# 02_FPGA_Clock_Flash.net
KiCad netlist of a schematic drawn in Altium Designer
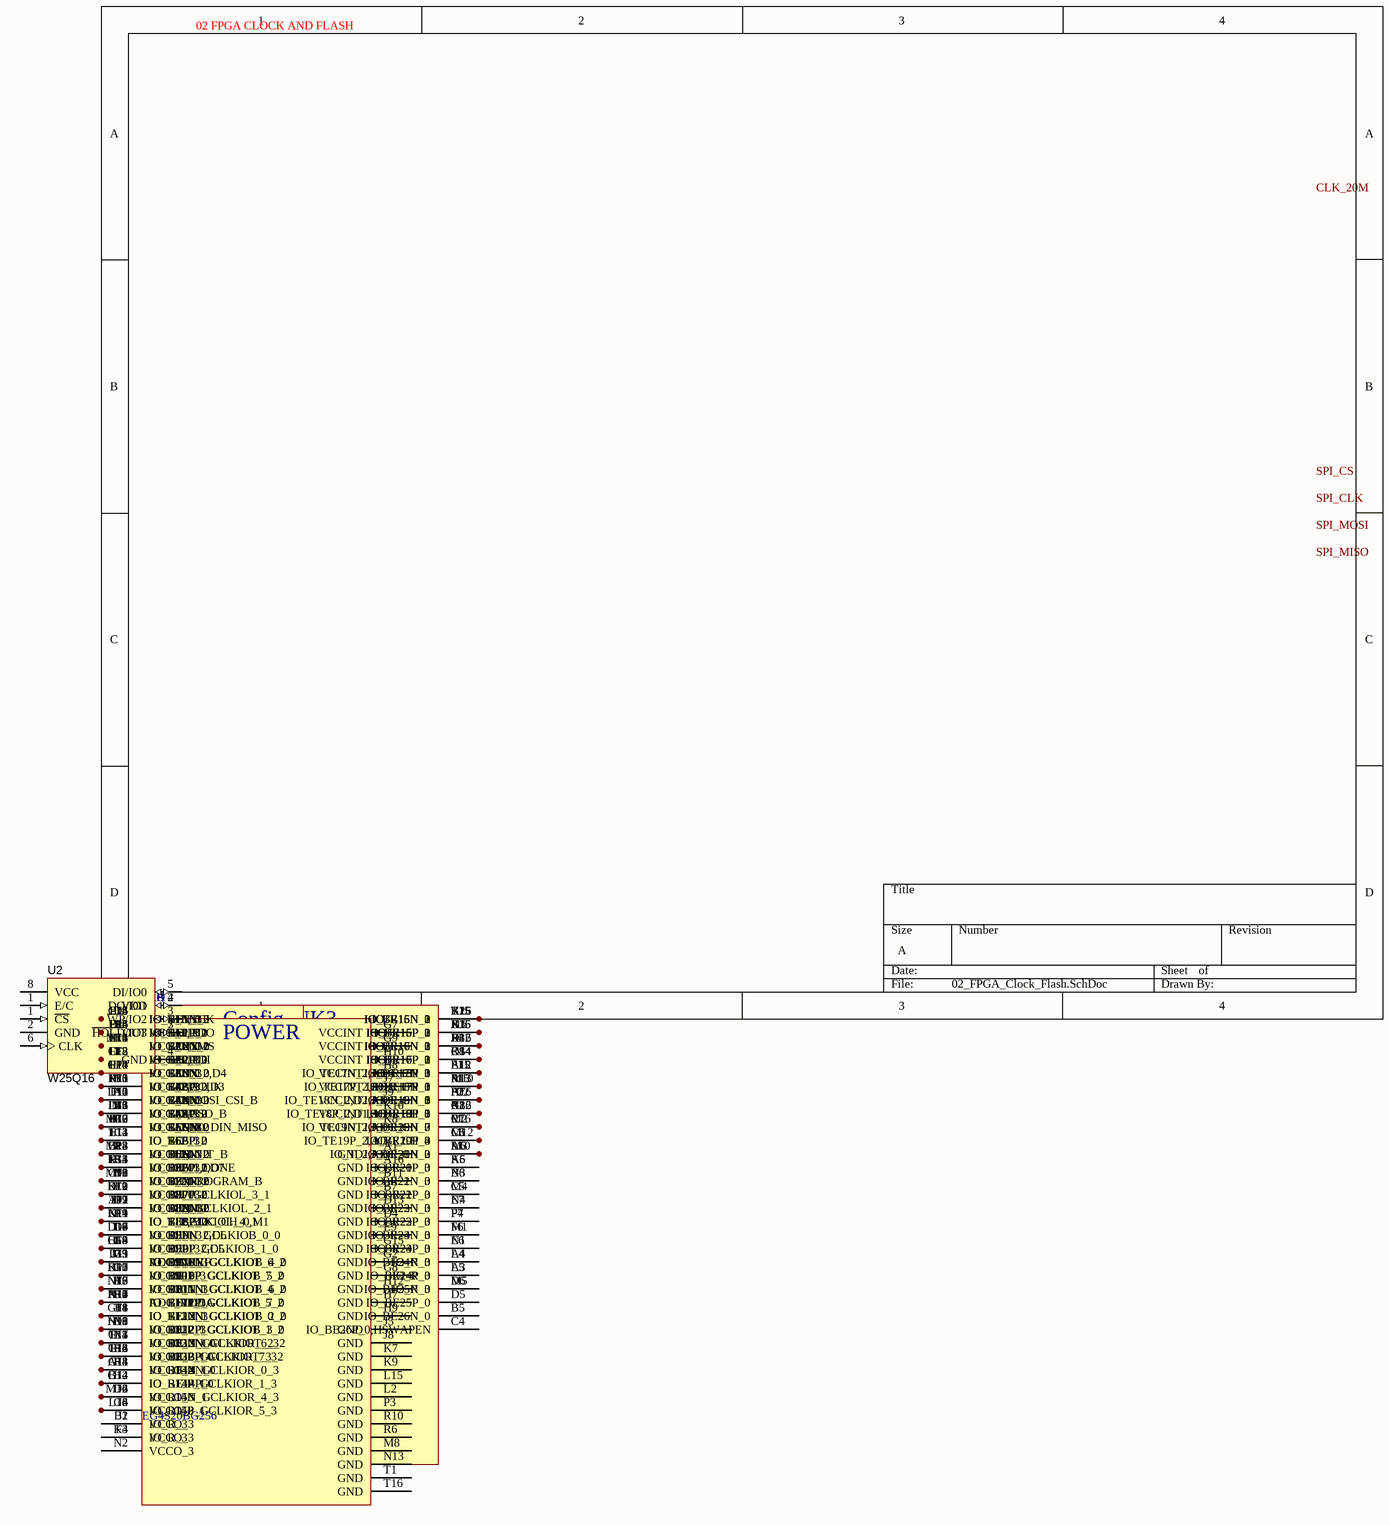
[diagram p0: 02_FPGA_Clock_Flash.SchDoc]

(export (version "E")
  (design (tool "Eeschema 10.0.6"))
  (components
    (comp (ref "U1") (value "EG4S20BG256") (footprint "FBGA256") (libsource (lib "") (part "EG4S20BG256_4")))
    (comp (ref "U2")
      (value "W25Q16")
      (footprint "MICT-MW-8_N")
      (description "2.5V 8M-Bit Serial Flash Memory with Dual and Quad SPI, SOIC-8")
      (fields
        (field (name "PARTNUMBER") "W25Q16")
        (field (name "MANUFACTURER") "Winbond")
        (field (name "SYMBOLCREATOR") "Altium")
        (field (name "PUBLISHER") "Texas Instruments")
      )
      (libsource (lib "Other_IC") (part "W25Q80BLSNIG"))
    )
    (comp (ref "Y1")
      (value "7X-50.000MBB-T")
      (footprint "XTAL_NX3225SA")
      (description "Crystal, 有源晶振，Sealed Locked 50MHz, 15pF, SMD")
      (fields
        (field (name "MANUFACTURER") "TXC Corporation")
        (field (name "FREQUENCY") "50MHz")
        (field (name "SYMBOLCREATOR") "a0799628")
        (field (name "PUBLISHER") "Texas Instruments")
      )
      (libsource (lib "HPA_SCHLIB") (part "7X-20.000MBB-T_1"))
    )
  )
  (nets
    (net (code "6") (name "Net-(U1A-IO_BE1N_0)") (class "Default")
      (node (ref "U1") (pin "C14") (pinfunction "IO_B_0,TCK_C14") (pintype "passive"))
      (node (ref "U1") (pin "D3") (pinfunction "IO_R1N_3_D3") (pintype "passive"))
      (node (ref "U1") (pin "F16") (pinfunction "IO_BE1N_0_F16") (pintype "passive"))
      (node (ref "U1") (pin "P15") (pinfunction "IO_L1N_1_P15") (pintype "passive"))
      (node (ref "U1") (pin "T4") (pinfunction "IO_TE1N_2_T4") (pintype "passive"))
    )
    (net (code "7") (name "Net-(U1A-IO_BE1P_0)") (class "Default")
      (node (ref "U1") (pin "B3") (pinfunction "IO_R1P_3_B3") (pintype "passive"))
      (node (ref "U1") (pin "E14") (pinfunction "IO_L_1,TDO_E14") (pintype "passive"))
      (node (ref "U1") (pin "E16") (pinfunction "IO_BE1P_0_E16") (pintype "passive"))
      (node (ref "U1") (pin "E5") (pinfunction "VCCAUX_E5") (pintype "passive"))
      (node (ref "U1") (pin "P16") (pinfunction "IO_L1P_1_P16") (pintype "passive"))
      (node (ref "U1") (pin "P6") (pinfunction "IO_TE1P_2_P6") (pintype "passive"))
    )
    (net (code "8") (name "Net-(U1A-IO_BE2N_0)") (class "Default")
      (node (ref "U1") (pin "A15") (pinfunction "IO_L_1,TMS_A15") (pintype "passive"))
      (node (ref "U1") (pin "E12") (pinfunction "IO_BE2N_0_E12") (pintype "passive"))
      (node (ref "U1") (pin "E4") (pinfunction "IO_R2N_3_E4") (pintype "passive"))
      (node (ref "U1") (pin "F11") (pinfunction "VCCAUX_F11") (pintype "passive"))
      (node (ref "U1") (pin "M11") (pinfunction "IO_L2N_1_M11") (pintype "passive"))
      (node (ref "U1") (pin "T6") (pinfunction "IO_TE2N_2_T6") (pintype "passive"))
    )
    (net (code "9") (name "Net-(U1A-IO_BE2P_0)") (class "Default")
      (node (ref "U1") (pin "C12") (pinfunction "IO_B_0,TDI_C12") (pintype "passive"))
      (node (ref "U1") (pin "E3") (pinfunction "IO_R2P_3_E3") (pintype "passive"))
      (node (ref "U1") (pin "F12") (pinfunction "IO_BE2P_0_F12") (pintype "passive"))
      (node (ref "U1") (pin "F8") (pinfunction "VCCAUX_F8") (pintype "passive"))
      (node (ref "U1") (pin "L12") (pinfunction "IO_L2P_1_L12") (pintype "passive"))
      (node (ref "U1") (pin "T5") (pinfunction "IO_TE2P_2_T5") (pintype "passive"))
    )
    (net (code "10") (name "Net-(U1A-IO_BE3N_0)") (class "Default")
      (node (ref "U1") (pin "F4") (pinfunction "IO_R3N_3_F4") (pintype "passive"))
      (node (ref "U1") (pin "G10") (pinfunction "VCCAUX_G10") (pintype "passive"))
      (node (ref "U1") (pin "H11") (pinfunction "IO_BE3N_0_H11") (pintype "passive"))
      (node (ref "U1") (pin "P14") (pinfunction "IO_L3N_1_P14") (pintype "passive"))
      (node (ref "U1") (pin "P5") (pinfunction "IO_TE3N_2,D4_P5") (pintype "passive"))
    )
    (net (code "11") (name "Net-(U1A-IO_BE3P_0)") (class "Default")
      (node (ref "U1") (pin "F10") (pinfunction "IO_BE3P_0_F10") (pintype "passive"))
      (node (ref "U1") (pin "F5") (pinfunction "IO_R3P_3_F5") (pintype "passive"))
      (node (ref "U1") (pin "H6") (pinfunction "VCCAUX_H6") (pintype "passive"))
      (node (ref "U1") (pin "K11") (pinfunction "IO_L4P_1_K11") (pintype "passive"))
      (node (ref "U1") (pin "N5") (pinfunction "IO_TE3P_2,D3_N5") (pintype "passive"))
      (node (ref "U1") (pin "R11") (pinfunction "IO_T_2,CCLK_R11") (pintype "passive"))
    )
    (net (code "12") (name "Net-(U1A-IO_BE4N_0)") (class "Default")
      (node (ref "U1") (pin "A2") (pinfunction "IO_R4N_3_A2") (pintype "passive"))
      (node (ref "U1") (pin "D12") (pinfunction "IO_BE4N_0_D12") (pintype "passive"))
      (node (ref "U1") (pin "J10") (pinfunction "VCCAUX_J10") (pintype "passive"))
      (node (ref "U1") (pin "J11") (pinfunction "IO_L4N_1_J11") (pintype "passive"))
      (node (ref "U1") (pin "N6") (pinfunction "IO_TE4N_2_N6") (pintype "passive"))
      (node (ref "U1") (pin "T10") (pinfunction "IO_T_2,MOSI_CSI_B_T10") (pintype "passive"))
    )
    (net (code "13") (name "Net-(U1A-IO_BE4P_0)") (class "Default")
      (node (ref "U1") (pin "B2") (pinfunction "IO_R4P_3_B2") (pintype "passive"))
      (node (ref "U1") (pin "D11") (pinfunction "IO_BE4P_0_D11") (pintype "passive"))
      (node (ref "U1") (pin "L13") (pinfunction "IO_L5P_1_L13") (pintype "passive"))
      (node (ref "U1") (pin "L6") (pinfunction "VCCAUX_L6") (pintype "passive"))
      (node (ref "U1") (pin "M6") (pinfunction "IO_TE4P_2_M6") (pintype "passive"))
      (node (ref "U1") (pin "T3") (pinfunction "IO_T_2,CSO_B_T3") (pintype "passive"))
    )
    (net (code "14") (name "Net-(U1A-IO_BE5N_0)") (class "Default")
      (node (ref "U1") (pin "C2") (pinfunction "IO_R5N_3_C2") (pintype "passive"))
      (node (ref "U1") (pin "E10") (pinfunction "IO_BE5N_0_E10") (pintype "passive"))
      (node (ref "U1") (pin "L9") (pinfunction "VCCAUX_L9") (pintype "passive"))
      (node (ref "U1") (pin "M13") (pinfunction "IO_L5N_1_M13") (pintype "passive"))
      (node (ref "U1") (pin "M7") (pinfunction "IO_TE5N_2_M7") (pintype "passive"))
      (node (ref "U1") (pin "P10") (pinfunction "IO_T_2,D0_DIN_MISO_P10") (pintype "passive"))
    )
    (net (code "15") (name "Net-(U1A-IO_BE5P_0)") (class "Default")
      (node (ref "U1") (pin "C3") (pinfunction "IO_R5P_3_C3") (pintype "passive"))
      (node (ref "U1") (pin "E11") (pinfunction "IO_BE5P_0_E11") (pintype "passive"))
      (node (ref "U1") (pin "L14") (pinfunction "IO_L6P_1_L14") (pintype "passive"))
      (node (ref "U1") (pin "T12") (pinfunction "IO_TE5P_2_T12") (pintype "passive"))
    )
    (net (code "16") (name "Net-(U1A-IO_BE6N_0)") (class "Default")
      (node (ref "U1") (pin "B13") (pinfunction "VCCO_0_B13") (pintype "passive"))
      (node (ref "U1") (pin "C13") (pinfunction "IO_BE6N_0_C13") (pintype "passive"))
      (node (ref "U1") (pin "E2") (pinfunction "IO_R6N_3_E2") (pintype "passive"))
      (node (ref "U1") (pin "M14") (pinfunction "IO_L6N_1_M14") (pintype "passive"))
      (node (ref "U1") (pin "P8") (pinfunction "IO_TE6N_2_P8") (pintype "passive"))
      (node (ref "U1") (pin "R3") (pinfunction "IO_T_2,INIT_B_R3") (pintype "passive"))
    )
    (net (code "17") (name "Net-(U1A-IO_BE6P_0)") (class "Default")
      (node (ref "U1") (pin "B4") (pinfunction "VCCO_0_B4") (pintype "passive"))
      (node (ref "U1") (pin "C1") (pinfunction "IO_R6P_3_C1") (pintype "passive"))
      (node (ref "U1") (pin "E13") (pinfunction "IO_BE6P_0_E13") (pintype "passive"))
      (node (ref "U1") (pin "K15") (pinfunction "IO_L7P_1_K15") (pintype "passive"))
      (node (ref "U1") (pin "P13") (pinfunction "IO_L3P_1,DONE_P13") (pintype "passive"))
      (node (ref "U1") (pin "R5") (pinfunction "IO_TE6P_2,D7_R5") (pintype "passive"))
    )
    (net (code "18") (name "Net-(U1A-IO_BE7N_0)") (class "Default")
      (node (ref "U1") (pin "B9") (pinfunction "VCCO_0_B9") (pintype "passive"))
      (node (ref "U1") (pin "C10") (pinfunction "IO_BE7N_0_C10") (pintype "passive"))
      (node (ref "U1") (pin "D1") (pinfunction "IO_R7N_3_D1") (pintype "passive"))
      (node (ref "U1") (pin "M15") (pinfunction "IO_L7N_1_M15") (pintype "passive"))
      (node (ref "U1") (pin "N8") (pinfunction "IO_TE7N_2_N8") (pintype "passive"))
      (node (ref "U1") (pin "T2") (pinfunction "IO_T_2,PROGRAM_B_T2") (pintype "passive"))
    )
    (net (code "19") (name "Net-(U1A-IO_BE7P_0)") (class "Default")
      (node (ref "U1") (pin "B12") (pinfunction "IO_BE7P_0_B12") (pintype "passive"))
      (node (ref "U1") (pin "D10") (pinfunction "VCCO_0_D10") (pintype "passive"))
      (node (ref "U1") (pin "E1") (pinfunction "IO_R7P_3_E1") (pintype "passive"))
      (node (ref "U1") (pin "K12") (pinfunction "IO_L8P_GCLKIOL_3_1_K12") (pintype "passive"))
      (node (ref "U1") (pin "T9") (pinfunction "IO_TE7P_2_T9") (pintype "passive"))
    )
    (net (code "20") (name "Net-(U1A-IO_BE8N_0)") (class "Default")
      (node (ref "U1") (pin "A11") (pinfunction "IO_BE8N_0_A11") (pintype "passive"))
      (node (ref "U1") (pin "D7") (pinfunction "VCCO_0_D7") (pintype "passive"))
      (node (ref "U1") (pin "F2") (pinfunction "IO_R8N_3_F2") (pintype "passive"))
      (node (ref "U1") (pin "J12") (pinfunction "IO_L8N_GCLKIOL_2_1_J12") (pintype "passive"))
      (node (ref "U1") (pin "P9") (pinfunction "IO_TE8N_2_P9") (pintype "passive"))
      (node (ref "U1") (pin "T11") (pinfunction "IO_T_2,M0_T11") (pintype "passive"))
    )
    (net (code "21") (name "Net-(U1A-IO_BE8P_0)") (class "Default")
      (node (ref "U1") (pin "C11") (pinfunction "IO_BE8P_0_C11") (pintype "passive"))
      (node (ref "U1") (pin "F1") (pinfunction "IO_R8P_3_F1") (pintype "passive"))
      (node (ref "U1") (pin "K14") (pinfunction "IO_L_GCLKIOL_4_1_K14") (pintype "passive"))
      (node (ref "U1") (pin "N11") (pinfunction "IO_T_2,ADC_CH_0,M1_N11") (pintype "passive"))
      (node (ref "U1") (pin "R9") (pinfunction "IO_TE8P_2_R9") (pintype "passive"))
    )
    (net (code "22") (name "Net-(U1A-IO_BE9N_GCLKIOB_0_0)") (class "Default")
      (node (ref "U1") (pin "D15") (pinfunction "VCCO_1_D15") (pintype "passive"))
      (node (ref "U1") (pin "D9") (pinfunction "IO_BE9N_GCLKIOB_0_0_D9") (pintype "passive"))
      (node (ref "U1") (pin "G6") (pinfunction "IO_R9N_3_G6") (pintype "passive"))
      (node (ref "U1") (pin "J14") (pinfunction "IO_L_1_J14") (pintype "passive"))
      (node (ref "U1") (pin "L7") (pinfunction "IO_TE9N_2,D6_L7") (pintype "passive"))
    )
    (net (code "23") (name "Net-(U1A-IO_BE9P_GCLKIOB_1_0)") (class "Default")
      (node (ref "U1") (pin "F9") (pinfunction "IO_BE9P_GCLKIOB_1_0_F9") (pintype "passive"))
      (node (ref "U1") (pin "G13") (pinfunction "VCCO_1_G13") (pintype "passive"))
      (node (ref "U1") (pin "G5") (pinfunction "IO_R9P_3_G5") (pintype "passive"))
      (node (ref "U1") (pin "H14") (pinfunction "IO_L_1_H14") (pintype "passive"))
      (node (ref "U1") (pin "L8") (pinfunction "IO_TE9P_2,D5_L8") (pintype "passive"))
    )
    (net (code "24") (name "Net-(U1A-IO_BE10N_GCLKIOB_4_0)") (class "Default")
      (node (ref "U1") (pin "C9") (pinfunction "IO_BE10N_GCLKIOB_4_0_C9") (pintype "passive"))
      (node (ref "U1") (pin "G3") (pinfunction "IO_R10N_3_G3") (pintype "passive"))
      (node (ref "U1") (pin "J13") (pinfunction "IO_L9N_1_J13") (pintype "passive"))
      (node (ref "U1") (pin "J15") (pinfunction "VCCO_1_J15") (pintype "passive"))
      (node (ref "U1") (pin "L11") (pinfunction "ADC_VREF_L11") (pintype "passive"))
      (node (ref "U1") (pin "M9") (pinfunction "IO_TE10N_GCLKIOT_6_2_M9") (pintype "passive"))
    )
    (net (code "25") (name "Net-(U1A-IO_BE10P_GCLKIOB_5_0)") (class "Default")
      (node (ref "U1") (pin "B10") (pinfunction "IO_BE10P_GCLKIOB_5_0_B10") (pintype "passive"))
      (node (ref "U1") (pin "G1") (pinfunction "IO_R10P_3_G1") (pintype "passive"))
      (node (ref "U1") (pin "H13") (pinfunction "IO_L9P_1_H13") (pintype "passive"))
      (node (ref "U1") (pin "K13") (pinfunction "VCCO_1_K13") (pintype "passive"))
      (node (ref "U1") (pin "P7") (pinfunction "IO_TE10P_GCLKIOT_7_2_P7") (pintype "passive"))
    )
    (net (code "26") (name "Net-(U1A-IO_BE11N_GCLKIOB_6_0)") (class "Default")
      (node (ref "U1") (pin "A9") (pinfunction "IO_BE11N_GCLKIOB_6_0_A9") (pintype "passive"))
      (node (ref "U1") (pin "H5") (pinfunction "IO_R11N_3_H5") (pintype "passive"))
      (node (ref "U1") (pin "N15") (pinfunction "VCCO_1_N15") (pintype "passive"))
      (node (ref "U1") (pin "N16") (pinfunction "IO_L10N_1_N16") (pintype "passive"))
      (node (ref "U1") (pin "T7") (pinfunction "IO_TE11N_GCLKIOT_4_2_T7") (pintype "passive"))
    )
    (net (code "27") (name "Net-(U1A-IO_BE11P_GCLKIOB_7_0)") (class "Default")
      (node (ref "U1") (pin "A10") (pinfunction "IO_BE11P_GCLKIOB_7_0_A10") (pintype "passive"))
      (node (ref "U1") (pin "H1") (pinfunction "IO_R11P_3_H1") (pintype "passive"))
      (node (ref "U1") (pin "N14") (pinfunction "IO_L10P_1_N14") (pintype "passive"))
      (node (ref "U1") (pin "R13") (pinfunction "ADC_VDDA_R13") (pintype "passive"))
      (node (ref "U1") (pin "R7") (pinfunction "IO_TE11P_GCLKIOT_5_2_R7") (pintype "passive"))
    )
    (net (code "28") (name "Net-(U1A-IO_BE12N_GCLKIOB_2_0)") (class "Default")
      (node (ref "U1") (pin "E8") (pinfunction "IO_BE12N_GCLKIOB_2_0_E8") (pintype "passive"))
      (node (ref "U1") (pin "G14") (pinfunction "IO_L11N_1_G14") (pintype "passive"))
      (node (ref "U1") (pin "J1") (pinfunction "IO_R12N_3_J1") (pintype "passive"))
      (node (ref "U1") (pin "T8") (pinfunction "IO_TE12N_GCLKIOT_0_2_T8") (pintype "passive"))
    )
    (net (code "29") (name "Net-(U1A-IO_BE12P_GCLKIOB_3_0)") (class "Default")
      (node (ref "U1") (pin "D8") (pinfunction "IO_BE12P_GCLKIOB_3_0_D8") (pintype "passive"))
      (node (ref "U1") (pin "H15") (pinfunction "IO_L11P_1_H15") (pintype "passive"))
      (node (ref "U1") (pin "K1") (pinfunction "IO_R12P_3_K1") (pintype "passive"))
      (node (ref "U1") (pin "N10") (pinfunction "VCCO_2_N10") (pintype "passive"))
      (node (ref "U1") (pin "N9") (pinfunction "IO_TE12P_GCLKIOT_1_2_N9") (pintype "passive"))
    )
    (net (code "30") (name "Net-(U1A-IO_BE13N_0)") (class "Default")
      (node (ref "U1") (pin "C15") (pinfunction "IO_BE13N_0_C15") (pintype "passive"))
      (node (ref "U1") (pin "F14") (pinfunction "IO_L12N_1_F14") (pintype "passive"))
      (node (ref "U1") (pin "L1") (pinfunction "IO_R13N_GCLKIOR_6_3_L1") (pintype "passive"))
      (node (ref "U1") (pin "N7") (pinfunction "VCCO_2_N7") (pintype "passive"))
      (node (ref "U1") (pin "T13") (pinfunction "IO_TE13N_GCLKIOT_2_2_T13") (pintype "passive"))
    )
    (net (code "31") (name "Net-(U1A-IO_BE13P_0)") (class "Default")
      (node (ref "U1") (pin "C16") (pinfunction "IO_BE13P_0_C16") (pintype "passive"))
      (node (ref "U1") (pin "F13") (pinfunction "IO_L12P_1_F13") (pintype "passive"))
      (node (ref "U1") (pin "H2") (pinfunction "IO_R13P_GCLKIOR_7_3_H2") (pintype "passive"))
      (node (ref "U1") (pin "R4") (pinfunction "VCCO_2_R4") (pintype "passive"))
      (node (ref "U1") (pin "T14") (pinfunction "IO_TE13P_GCLKIOT_3_2_T14") (pintype "passive"))
    )
    (net (code "32") (name "Net-(U1A-IO_BE14N_0)") (class "Default")
      (node (ref "U1") (pin "A14") (pinfunction "IO_BE14N_0_A14") (pintype "passive"))
      (node (ref "U1") (pin "G11") (pinfunction "IO_L13N_1_G11") (pintype "passive"))
      (node (ref "U1") (pin "H3") (pinfunction "IO_R14N_GCLKIOR_0_3_H3") (pintype "passive"))
      (node (ref "U1") (pin "R8") (pinfunction "VCCO_2_R8") (pintype "passive"))
    )
    (net (code "33") (name "Net-(U1A-IO_BE14P_0)") (class "Default")
      (node (ref "U1") (pin "B14") (pinfunction "IO_BE14P_0_B14") (pintype "passive"))
      (node (ref "U1") (pin "G12") (pinfunction "IO_L13P_1_G12") (pintype "passive"))
      (node (ref "U1") (pin "H4") (pinfunction "IO_R14P_GCLKIOR_1_3_H4") (pintype "passive"))
    )
    (net (code "34") (name "Net-(U1A-IO_BE15N_0)") (class "Default")
      (node (ref "U1") (pin "B15") (pinfunction "IO_BE15N_0_B15") (pintype "passive"))
      (node (ref "U1") (pin "K16") (pinfunction "IO_L15N_1_K16") (pintype "passive"))
      (node (ref "U1") (pin "K2") (pinfunction "IO_R16N_3_K2") (pintype "passive"))
      (node (ref "U1") (pin "T15") (pinfunction "IO_TE15N_2_T15") (pintype "passive"))
    )
    (net (code "35") (name "Net-(U1A-IO_BE15P_0)") (class "Default")
      (node (ref "U1") (pin "B16") (pinfunction "IO_BE15P_0_B16") (pintype "passive"))
      (node (ref "U1") (pin "J16") (pinfunction "IO_L15P_1_J16") (pintype "passive"))
      (node (ref "U1") (pin "K3") (pinfunction "IO_R16P_3_K3") (pintype "passive"))
      (node (ref "U1") (pin "R15") (pinfunction "IO_TE15P_2_R15") (pintype "passive"))
    )
    (net (code "36") (name "Net-(U1A-IO_BE16N_0)") (class "Default")
      (node (ref "U1") (pin "B8") (pinfunction "IO_BE16N_0_B8") (pintype "passive"))
      (node (ref "U1") (pin "D16") (pinfunction "IO_L16N_1_D16") (pintype "passive"))
      (node (ref "U1") (pin "J6") (pinfunction "IO_R17N_3_J6") (pintype "passive"))
      (node (ref "U1") (pin "R12") (pinfunction "IO_TE16N_2_R12") (pintype "passive"))
    )
    (net (code "37") (name "Net-(U1A-IO_BE16P_0)") (class "Default")
      (node (ref "U1") (pin "C8") (pinfunction "IO_BE16P_0_C8") (pintype "passive"))
      (node (ref "U1") (pin "D14") (pinfunction "IO_L16P_1_D14") (pintype "passive"))
      (node (ref "U1") (pin "K5") (pinfunction "IO_R17P_3_K5") (pintype "passive"))
      (node (ref "U1") (pin "R14") (pinfunction "IO_TE16P_2_R14") (pintype "passive"))
    )
    (net (code "38") (name "Net-(U1A-IO_BE17N_0)") (class "Default")
      (node (ref "U1") (pin "A12") (pinfunction "IO_BE17N_0_A12") (pintype "passive"))
      (node (ref "U1") (pin "E15") (pinfunction "IO_L17N_1_E15") (pintype "passive"))
      (node (ref "U1") (pin "P1") (pinfunction "IO_R18P_3_P1") (pintype "passive"))
      (node (ref "U1") (pin "P11") (pinfunction "IO_TE17N_2,ADC_CH_3_P11") (pintype "passive"))
    )
    (net (code "39") (name "Net-(U1A-IO_BE17P_0)") (class "Default")
      (node (ref "U1") (pin "A13") (pinfunction "IO_BE17P_0_A13") (pintype "passive"))
      (node (ref "U1") (pin "F15") (pinfunction "IO_L17P_1_F15") (pintype "passive"))
      (node (ref "U1") (pin "M10") (pinfunction "IO_TE17P_2,ADC_CH_1_M10") (pintype "passive"))
      (node (ref "U1") (pin "R1") (pinfunction "IO_R18N_3_R1") (pintype "passive"))
    )
    (net (code "40") (name "Net-(U1A-IO_BE18N_0)") (class "Default")
      (node (ref "U1") (pin "A7") (pinfunction "IO_BE18N_0_A7") (pintype "passive"))
      (node (ref "U1") (pin "H16") (pinfunction "IO_L18N_1_H16") (pintype "passive"))
      (node (ref "U1") (pin "P12") (pinfunction "IO_TE18N_2,D2,ADC_CH_6_P12") (pintype "passive"))
      (node (ref "U1") (pin "P2") (pinfunction "IO_R19N_3_P2") (pintype "passive"))
    )
    (net (code "41") (name "Net-(U1A-IO_BE18P_0)") (class "Default")
      (node (ref "U1") (pin "A8") (pinfunction "IO_BE18P_0_A8") (pintype "passive"))
      (node (ref "U1") (pin "G16") (pinfunction "IO_L18P_1_G16") (pintype "passive"))
      (node (ref "U1") (pin "N12") (pinfunction "IO_TE18P_2,D1,ADC_CH_5_N12") (pintype "passive"))
      (node (ref "U1") (pin "R2") (pinfunction "IO_R19P_3_R2") (pintype "passive"))
    )
    (net (code "42") (name "Net-(U1A-IO_BE19N_0)") (class "Default")
      (node (ref "U1") (pin "C7") (pinfunction "IO_BE19N_0_C7") (pintype "passive"))
      (node (ref "U1") (pin "M2") (pinfunction "IO_R20N_3_M2") (pintype "passive"))
      (node (ref "U1") (pin "R16") (pinfunction "IO_TE19N_2,ADC_CH_7_R16") (pintype "passive"))
    )
    (net (code "43") (name "Net-(U1A-IO_BE19P_0)") (class "Default")
      (node (ref "U1") (pin "C6") (pinfunction "IO_BE19P_0_C6") (pintype "passive"))
      (node (ref "U1") (pin "L3") (pinfunction "IO_R20P_3_L3") (pintype "passive"))
      (node (ref "U1") (pin "M12") (pinfunction "IO_TE19P_2,ADC_CH_4_M12") (pintype "passive"))
    )
    (net (code "44") (name "Net-(U1A-IO_BE20N_0)") (class "Default")
      (node (ref "U1") (pin "A6") (pinfunction "IO_BE20N_0_A6") (pintype "passive"))
      (node (ref "U1") (pin "L10") (pinfunction "IO_T_2,ADC_CH_2_L10") (pintype "passive"))
      (node (ref "U1") (pin "M3") (pinfunction "IO_R21N_3_M3") (pintype "passive"))
    )
    (net (code "45") (name "Net-(U1A-IO_BE20P_0)") (class "Default")
      (node (ref "U1") (pin "A5") (pinfunction "IO_BE20P_0_A5") (pintype "passive"))
      (node (ref "U1") (pin "K6") (pinfunction "IO_R21P_3_K6") (pintype "passive"))
    )
    (net (code "46") (name "Net-(U1A-IO_BE21N_0)") (class "Default")
      (node (ref "U1") (pin "B6") (pinfunction "IO_BE21N_0_B6") (pintype "passive"))
      (node (ref "U1") (pin "N3") (pinfunction "IO_R22N_3_N3") (pintype "passive"))
    )
    (net (code "47") (name "Net-(U1A-IO_BE21P_0)") (class "Default")
      (node (ref "U1") (pin "C5") (pinfunction "IO_BE21P_0_C5") (pintype "passive"))
      (node (ref "U1") (pin "M4") (pinfunction "IO_R22P_3_M4") (pintype "passive"))
    )
    (net (code "48") (name "Net-(U1A-IO_BE22N_0)") (class "Default")
      (node (ref "U1") (pin "E7") (pinfunction "IO_BE22N_0_E7") (pintype "passive"))
      (node (ref "U1") (pin "N4") (pinfunction "IO_R23N_3_N4") (pintype "passive"))
    )
    (net (code "49") (name "Net-(U1A-IO_BE22P_0)") (class "Default")
      (node (ref "U1") (pin "F7") (pinfunction "IO_BE22P_0_F7") (pintype "passive"))
      (node (ref "U1") (pin "P4") (pinfunction "IO_R23P_3_P4") (pintype "passive"))
    )
    (net (code "50") (name "Net-(U1A-IO_BE23N_0)") (class "Default")
      (node (ref "U1") (pin "F6") (pinfunction "IO_BE23N_0_F6") (pintype "passive"))
      (node (ref "U1") (pin "M1") (pinfunction "IO_R24N_3_M1") (pintype "passive"))
    )
    (net (code "51") (name "Net-(U1A-IO_BE23P_0)") (class "Default")
      (node (ref "U1") (pin "E6") (pinfunction "IO_BE23P_0_E6") (pintype "passive"))
      (node (ref "U1") (pin "N1") (pinfunction "IO_R24P_3_N1") (pintype "passive"))
    )
    (net (code "52") (name "Net-(U1A-IO_BE24N_0)") (class "Default")
      (node (ref "U1") (pin "A4") (pinfunction "IO_BE24N_0_A4") (pintype "passive"))
      (node (ref "U1") (pin "L4") (pinfunction "IO_R_3_L4") (pintype "passive"))
    )
    (net (code "53") (name "Net-(U1A-IO_BE24P_0)") (class "Default")
      (node (ref "U1") (pin "A3") (pinfunction "IO_BE24P_0_A3") (pintype "passive"))
      (node (ref "U1") (pin "L5") (pinfunction "IO_R_3_L5") (pintype "passive"))
    )
    (net (code "54") (name "Net-(U1A-IO_BE25N_0)") (class "Default")
      (node (ref "U1") (pin "D6") (pinfunction "IO_BE25N_0_D6") (pintype "passive"))
      (node (ref "U1") (pin "M5") (pinfunction "IO_R_3_M5") (pintype "passive"))
    )
    (net (code "55") (name "Net-(U1B-IO_L14N_1)") (class "Default")
      (node (ref "U1") (pin "D2") (pinfunction "VCCO_3_D2") (pintype "passive"))
      (node (ref "U1") (pin "J4") (pinfunction "IO_R15N_GCLKIOR_4_3_J4") (pintype "passive"))
      (node (ref "U1") (pin "M16") (pinfunction "IO_L14N_1_M16") (pintype "passive"))
    )
    (net (code "56") (name "Net-(U1B-IO_L14P_1)") (class "Default")
      (node (ref "U1") (pin "G4") (pinfunction "VCCO_3_G4") (pintype "passive"))
      (node (ref "U1") (pin "J3") (pinfunction "IO_R15P_GCLKIOR_5_3_J3") (pintype "passive"))
      (node (ref "U1") (pin "L16") (pinfunction "IO_L14P_1_L16") (pintype "passive"))
    )
    (net (code "57") (name "Net-(U1D-IO_R_3-PadB1)") (class "Default")
      (node (ref "U1") (pin "B1") (pinfunction "IO_R_3_B1") (pintype "passive"))
      (node (ref "U1") (pin "J2") (pinfunction "VCCO_3_J2") (pintype "passive"))
    )
    (net (code "58") (name "Net-(U1D-IO_R_3-PadF3)") (class "Default")
      (node (ref "U1") (pin "F3") (pinfunction "IO_R_3_F3") (pintype "passive"))
      (node (ref "U1") (pin "K4") (pinfunction "VCCO_3_K4") (pintype "passive"))
    )
    (net (code "59") (name "Net-(U2-DO{slash}IO1)") (class "Default")
      (node (ref "U2") (pin "2") (pinfunction "DO/IO1_2") (pintype "bidirectional"))
      (node (ref "Y1") (pin "4") (pinfunction "VDD_4") (pintype "power_in"))
    )
    (net (code "60") (name "Net-(U2-~{HOLD}{slash}IO3)") (class "Default")
      (node (ref "U2") (pin "7") (pinfunction "~{HOLD}/IO3_7") (pintype "bidirectional"))
      (node (ref "Y1") (pin "3") (pinfunction "OUT_3") (pintype "output"))
    )
    (net (code "61") (name "unconnected-(U1A-IO_BE25P_0-PadD5)") (class "Default")
      (node (ref "U1") (pin "D5") (pinfunction "IO_BE25P_0_D5") (pintype "passive"))
    )
    (net (code "62") (name "unconnected-(U1A-IO_BE26N_0-PadB5)") (class "Default")
      (node (ref "U1") (pin "B5") (pinfunction "IO_BE26N_0_B5") (pintype "passive"))
    )
    (net (code "63") (name "unconnected-(U1A-IO_BE26P_0,HSWAPEN-PadC4)") (class "Default")
      (node (ref "U1") (pin "C4") (pinfunction "IO_BE26P_0,HSWAPEN_C4") (pintype "passive"))
    )
    (net (code "64") (name "unconnected-(U1F-GND-PadA1)") (class "Default")
      (node (ref "U1") (pin "A1") (pinfunction "GND_A1") (pintype "passive"))
    )
    (net (code "65") (name "unconnected-(U1F-GND-PadA16)") (class "Default")
      (node (ref "U1") (pin "A16") (pinfunction "GND_A16") (pintype "passive"))
    )
    (net (code "66") (name "unconnected-(U1F-GND-PadB7)") (class "Default")
      (node (ref "U1") (pin "B7") (pinfunction "GND_B7") (pintype "passive"))
    )
    (net (code "67") (name "unconnected-(U1F-GND-PadB11)") (class "Default")
      (node (ref "U1") (pin "B11") (pinfunction "GND_B11") (pintype "passive"))
    )
    (net (code "68") (name "unconnected-(U1F-GND-PadD4)") (class "Default")
      (node (ref "U1") (pin "D4") (pinfunction "GND_D4") (pintype "passive"))
    )
    (net (code "69") (name "unconnected-(U1F-GND-PadD13)") (class "Default")
      (node (ref "U1") (pin "D13") (pinfunction "GND_D13") (pintype "passive"))
    )
    (net (code "70") (name "unconnected-(U1F-GND-PadE9)") (class "Default")
      (node (ref "U1") (pin "E9") (pinfunction "GND_E9") (pintype "passive"))
    )
    (net (code "71") (name "unconnected-(U1F-GND-PadG2)") (class "Default")
      (node (ref "U1") (pin "G2") (pinfunction "GND_G2") (pintype "passive"))
    )
    (net (code "72") (name "unconnected-(U1F-GND-PadG8)") (class "Default")
      (node (ref "U1") (pin "G8") (pinfunction "GND_G8") (pintype "passive"))
    )
    (net (code "73") (name "unconnected-(U1F-GND-PadG15)") (class "Default")
      (node (ref "U1") (pin "G15") (pinfunction "GND_G15") (pintype "passive"))
    )
    (net (code "74") (name "unconnected-(U1F-GND-PadH7)") (class "Default")
      (node (ref "U1") (pin "H7") (pinfunction "GND_H7") (pintype "passive"))
    )
    (net (code "75") (name "unconnected-(U1F-GND-PadH9)") (class "Default")
      (node (ref "U1") (pin "H9") (pinfunction "GND_H9") (pintype "passive"))
    )
    (net (code "76") (name "unconnected-(U1F-GND-PadH12)") (class "Default")
      (node (ref "U1") (pin "H12") (pinfunction "GND_H12") (pintype "passive"))
    )
    (net (code "77") (name "unconnected-(U1F-GND-PadJ5)") (class "Default")
      (node (ref "U1") (pin "J5") (pinfunction "GND_J5") (pintype "passive"))
    )
    (net (code "78") (name "unconnected-(U1F-GND-PadJ8)") (class "Default")
      (node (ref "U1") (pin "J8") (pinfunction "GND_J8") (pintype "passive"))
    )
    (net (code "79") (name "unconnected-(U1F-GND-PadK7)") (class "Default")
      (node (ref "U1") (pin "K7") (pinfunction "GND_K7") (pintype "passive"))
    )
    (net (code "80") (name "unconnected-(U1F-GND-PadK9)") (class "Default")
      (node (ref "U1") (pin "K9") (pinfunction "GND_K9") (pintype "passive"))
    )
    (net (code "81") (name "unconnected-(U1F-GND-PadL2)") (class "Default")
      (node (ref "U1") (pin "L2") (pinfunction "GND_L2") (pintype "passive"))
    )
    (net (code "82") (name "unconnected-(U1F-GND-PadL15)") (class "Default")
      (node (ref "U1") (pin "L15") (pinfunction "GND_L15") (pintype "passive"))
    )
    (net (code "83") (name "unconnected-(U1F-GND-PadM8)") (class "Default")
      (node (ref "U1") (pin "M8") (pinfunction "GND_M8") (pintype "passive"))
    )
    (net (code "84") (name "unconnected-(U1F-GND-PadN13)") (class "Default")
      (node (ref "U1") (pin "N13") (pinfunction "GND_N13") (pintype "passive"))
    )
    (net (code "85") (name "unconnected-(U1F-GND-PadP3)") (class "Default")
      (node (ref "U1") (pin "P3") (pinfunction "GND_P3") (pintype "passive"))
    )
    (net (code "86") (name "unconnected-(U1F-GND-PadR6)") (class "Default")
      (node (ref "U1") (pin "R6") (pinfunction "GND_R6") (pintype "passive"))
    )
    (net (code "87") (name "unconnected-(U1F-GND-PadR10)") (class "Default")
      (node (ref "U1") (pin "R10") (pinfunction "GND_R10") (pintype "passive"))
    )
    (net (code "88") (name "unconnected-(U1F-GND-PadT1)") (class "Default")
      (node (ref "U1") (pin "T1") (pinfunction "GND_T1") (pintype "passive"))
    )
    (net (code "89") (name "unconnected-(U1F-GND-PadT16)") (class "Default")
      (node (ref "U1") (pin "T16") (pinfunction "GND_T16") (pintype "passive"))
    )
    (net (code "90") (name "unconnected-(U1F-VCCINT-PadG7)") (class "Default")
      (node (ref "U1") (pin "G7") (pinfunction "VCCINT_G7") (pintype "passive"))
    )
    (net (code "91") (name "unconnected-(U1F-VCCINT-PadG9)") (class "Default")
      (node (ref "U1") (pin "G9") (pinfunction "VCCINT_G9") (pintype "passive"))
    )
    (net (code "92") (name "unconnected-(U1F-VCCINT-PadH8)") (class "Default")
      (node (ref "U1") (pin "H8") (pinfunction "VCCINT_H8") (pintype "passive"))
    )
    (net (code "93") (name "unconnected-(U1F-VCCINT-PadH10)") (class "Default")
      (node (ref "U1") (pin "H10") (pinfunction "VCCINT_H10") (pintype "passive"))
    )
    (net (code "94") (name "unconnected-(U1F-VCCINT-PadJ7)") (class "Default")
      (node (ref "U1") (pin "J7") (pinfunction "VCCINT_J7") (pintype "passive"))
    )
    (net (code "95") (name "unconnected-(U1F-VCCINT-PadJ9)") (class "Default")
      (node (ref "U1") (pin "J9") (pinfunction "VCCINT_J9") (pintype "passive"))
    )
    (net (code "96") (name "unconnected-(U1F-VCCINT-PadK8)") (class "Default")
      (node (ref "U1") (pin "K8") (pinfunction "VCCINT_K8") (pintype "passive"))
    )
    (net (code "97") (name "unconnected-(U1F-VCCINT-PadK10)") (class "Default")
      (node (ref "U1") (pin "K10") (pinfunction "VCCINT_K10") (pintype "passive"))
    )
    (net (code "98") (name "unconnected-(U1F-VCCO_3-PadN2)") (class "Default")
      (node (ref "U1") (pin "N2") (pinfunction "VCCO_3_N2") (pintype "passive"))
    )
    (net (code "99") (name "unconnected-(U2-CLK-Pad6)") (class "Default")
      (node (ref "U2") (pin "6") (pinfunction "CLK_6") (pintype "input"))
    )
    (net (code "100") (name "unconnected-(U2-DI{slash}IO0-Pad5)") (class "Default")
      (node (ref "U2") (pin "5") (pinfunction "DI/IO0_5") (pintype "bidirectional"))
    )
    (net (code "101") (name "unconnected-(U2-GND-Pad4)") (class "Default")
      (node (ref "U2") (pin "4") (pinfunction "GND_4") (pintype "power_in"))
    )
    (net (code "102") (name "unconnected-(U2-VCC-Pad8)") (class "Default")
      (node (ref "U2") (pin "8") (pinfunction "VCC_8") (pintype "power_in"))
    )
    (net (code "103") (name "unconnected-(U2-~{CS}-Pad1)") (class "Default")
      (node (ref "U2") (pin "1") (pinfunction "~{CS}_1") (pintype "input"))
    )
    (net (code "104") (name "unconnected-(U2-~{WP}{slash}IO2-Pad3)") (class "Default")
      (node (ref "U2") (pin "3") (pinfunction "~{WP}/IO2_3") (pintype "bidirectional"))
    )
    (net (code "105") (name "unconnected-(Y1-E{slash}C-Pad1)") (class "Default")
      (node (ref "Y1") (pin "1") (pinfunction "E/C_1") (pintype "input"))
    )
    (net (code "106") (name "unconnected-(Y1-GND-Pad2)") (class "Default")
      (node (ref "Y1") (pin "2") (pinfunction "GND_2") (pintype "power_in"))
    )
  )
)
